# PSU.net
KiCad netlist of a schematic drawn in Altium Designer
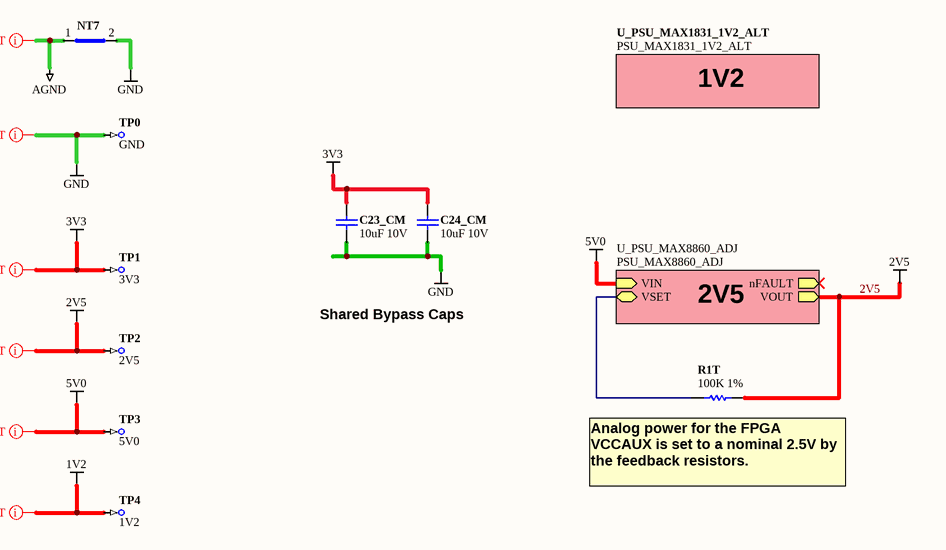
[diagram p0: PSU.SCHDOC]

(export (version "E")
  (design (tool "Eeschema 10.0.6"))
  (components
    (comp (ref "C23_CM")
      (value "10uF 10V")
      (footprint "CAPC2012-STAR")
      (description "Capacitor, Ceramic, 10uF 10% 10V 0805 (2012) X5R")
      (fields (field (name "TOLERANCE") "10 %"))
      (libsource (lib "AltiumDesignLibrary") (part "CAP-NP"))
    )
    (comp (ref "C24_CM")
      (value "10uF 10V")
      (footprint "CAPC2012-STAR")
      (description "Capacitor, Ceramic, 10uF 10% 10V 0805 (2012) X5R")
      (fields (field (name "TOLERANCE") "10 %"))
      (libsource (lib "AltiumDesignLibrary") (part "CAP-NP"))
    )
    (comp (ref "NT7")
      (value "Net Tie SMT2")
      (footprint "NETTIE-SMT2-8X8")
      (description "Net-Tie, Surface Mount, 2 x 0.4mm x 0.2mm SMT Pads - For 0.2mm Track")
      (libsource (lib "AltiumDesignLibrary") (part "NETTIE-SMT2"))
    )
    (comp (ref "R1T")
      (value "100K 1%")
      (footprint "RESC1005-STAR")
      (description "Resistor, 100K 1% 0402 (1005)")
      (fields (field (name "TOLERANCE") "1 %"))
      (libsource (lib "AltiumDesignLibrary") (part "RES"))
    )
    (comp (ref "TP0")
      (value "GND")
      (footprint "TestPin")
      (description "Test Point, PCB Mount with Silkscreen Box")
      (libsource (lib "AltiumDesignLibrary") (part "TestPin"))
    )
    (comp (ref "TP1")
      (value "3V3")
      (footprint "TestPin")
      (description "Test Point, PCB Mount with Silkscreen Box")
      (libsource (lib "AltiumDesignLibrary") (part "TestPin"))
    )
    (comp (ref "TP2")
      (value "2V5")
      (footprint "TestPin")
      (description "Test Point, PCB Mount with Silkscreen Box")
      (libsource (lib "AltiumDesignLibrary") (part "TestPin"))
    )
    (comp (ref "TP3")
      (value "5V0")
      (footprint "TestPin")
      (description "Test Point, PCB Mount with Silkscreen Box")
      (libsource (lib "AltiumDesignLibrary") (part "TestPin"))
    )
    (comp (ref "TP4")
      (value "1V2")
      (footprint "TestPin")
      (description "Test Point, PCB Mount with Silkscreen Box")
      (libsource (lib "AltiumDesignLibrary") (part "TestPin"))
    )
  )
  (nets
    (net (code "1") (name "/VSET") (class "Default")
      (node (ref "R1T") (pin "1") (pinfunction "1_1") (pintype "passive"))
    )
    (net (code "3") (name "1V2") (class "Default")
      (node (ref "TP4") (pin "1") (pinfunction "1_1") (pintype "input"))
    )
    (net (code "4") (name "2V5") (class "Default")
      (node (ref "R1T") (pin "2") (pinfunction "2_2") (pintype "passive"))
      (node (ref "TP2") (pin "1") (pinfunction "1_1") (pintype "input"))
    )
    (net (code "5") (name "3V3") (class "Default")
      (node (ref "C23_CM") (pin "1") (pinfunction "1_1") (pintype "passive"))
      (node (ref "C24_CM") (pin "1") (pinfunction "1_1") (pintype "passive"))
      (node (ref "TP1") (pin "1") (pinfunction "1_1") (pintype "input"))
    )
    (net (code "6") (name "5V0") (class "Default")
      (node (ref "TP3") (pin "1") (pinfunction "1_1") (pintype "input"))
    )
    (net (code "7") (name "AGND") (class "Default")
      (node (ref "NT7") (pin "1") (pinfunction "Net1_1") (pintype "passive"))
    )
    (net (code "8") (name "GND") (class "Default")
      (node (ref "C23_CM") (pin "2") (pinfunction "2_2") (pintype "passive"))
      (node (ref "C24_CM") (pin "2") (pinfunction "2_2") (pintype "passive"))
      (node (ref "NT7") (pin "2") (pinfunction "Net2_2") (pintype "passive"))
      (node (ref "TP0") (pin "1") (pinfunction "1_1") (pintype "input"))
    )
  )
)
